# esp8266_shield.net
KiCad netlist of a schematic drawn in Altium Designer
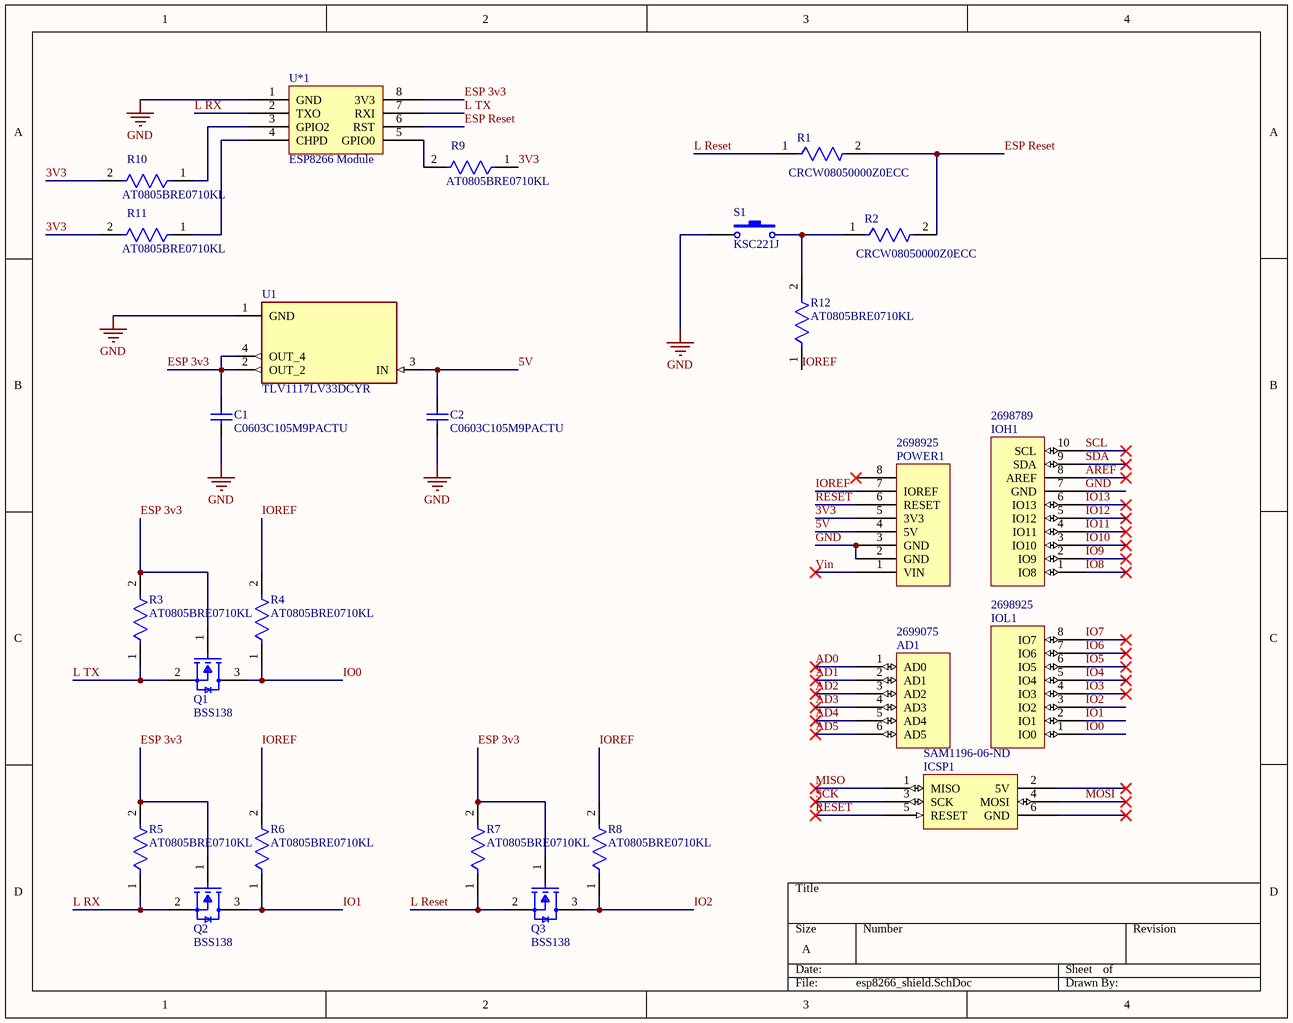
[diagram p0: esp8266_shield.SchDoc]

(export (version "E")
  (design (tool "Eeschema 10.0.6"))
  (components
    (comp (ref "AD1")
      (value "AD")
      (footprint "Header:Header 6x1 8.5mm")
      (fields (field (name "SUPPLIER PART NUMBER 4") "2699075"))
      (libsource (lib "Header") (part "AD"))
    )
    (comp (ref "C1")
      (value "C0603C105M9PACTU")
      (footprint "CAPC1608X90X35ML15T15")
      (fields (field (name "MANUFACTURER") "Kemet"))
      (libsource (lib "Altium Content Vault") (part "CAP"))
    )
    (comp (ref "C2")
      (value "C0603C105M9PACTU")
      (footprint "CAPC1608X90X35ML15T15")
      (fields (field (name "MANUFACTURER") "Kemet"))
      (libsource (lib "Altium Content Vault") (part "CAP"))
    )
    (comp (ref "ICSP1")
      (value "ICSP")
      (footprint "ICSP")
      (fields (field (name "SUPPLIER PART NUMBER 5") "SAM1196-06-ND"))
      (libsource (lib "Header") (part "ICSP"))
    )
    (comp (ref "IOH1")
      (value "IOH")
      (footprint "Header 10x1 8.5mm")
      (fields (field (name "SUPPLIER PART NUMBER 3") "2698789"))
      (libsource (lib "Header") (part "IOH"))
    )
    (comp (ref "IOL1")
      (value "IOL")
      (footprint "Header 8x1 8.5mm")
      (fields (field (name "SUPPLIER PART NUMBER 4") "2698925"))
      (libsource (lib "Header") (part "IOL"))
    )
    (comp (ref "POWER1")
      (value "POWER_UNO")
      (footprint "Header 8x1 8.5mm")
      (fields (field (name "SUPPLIER PART NUMBER 4") "2698925"))
      (libsource (lib "Header") (part "POWER_UNO"))
    )
    (comp (ref "Q1")
      (value "BSS138")
      (footprint "FP-318-08-IPC_B")
      (description "MOSFET N-CH 50V 220MA SOT-23")
      (libsource (lib "Altium Content Vault") (part "3b9c635fedb024a5347a57b145af9cc"))
    )
    (comp (ref "Q2")
      (value "BSS138")
      (footprint "FP-318-08-IPC_B")
      (description "MOSFET N-CH 50V 220MA SOT-23")
      (libsource (lib "Altium Content Vault") (part "3b9c635fedb024a5347a57b145af9cc"))
    )
    (comp (ref "Q3")
      (value "BSS138")
      (footprint "FP-318-08-IPC_B")
      (description "MOSFET N-CH 50V 220MA SOT-23")
      (libsource (lib "Altium Content Vault") (part "3b9c635fedb024a5347a57b145af9cc"))
    )
    (comp (ref "R1")
      (value "CRCW08050000Z0ECC")
      (footprint "FP-CRCW0805-Ce3-MFG")
      (libsource (lib "Altium Content Vault") (part "1029c3af85768c4190bb7ad29bc67b5"))
    )
    (comp (ref "R2")
      (value "CRCW08050000Z0ECC")
      (footprint "FP-CRCW0805-Ce3-MFG")
      (libsource (lib "Altium Content Vault") (part "1029c3af85768c4190bb7ad29bc67b5"))
    )
    (comp (ref "R3")
      (value "AT0805BRE0710KL")
      (footprint "FP-AT0805-IPC_C")
      (description "Thin Film Chip Resistors Automotive Grade 10kΩ 0.1% 50ppm/°C 0805")
      (libsource (lib "Altium Content Vault") (part "1029c3af85768c4190bb7ad29bc67b5"))
    )
    (comp (ref "R4")
      (value "AT0805BRE0710KL")
      (footprint "FP-AT0805-IPC_C")
      (description "Thin Film Chip Resistors Automotive Grade 10kΩ 0.1% 50ppm/°C 0805")
      (libsource (lib "Altium Content Vault") (part "1029c3af85768c4190bb7ad29bc67b5"))
    )
    (comp (ref "R5")
      (value "AT0805BRE0710KL")
      (footprint "FP-AT0805-IPC_C")
      (description "Thin Film Chip Resistors Automotive Grade 10kΩ 0.1% 50ppm/°C 0805")
      (libsource (lib "Altium Content Vault") (part "1029c3af85768c4190bb7ad29bc67b5"))
    )
    (comp (ref "R6")
      (value "AT0805BRE0710KL")
      (footprint "FP-AT0805-IPC_C")
      (description "Thin Film Chip Resistors Automotive Grade 10kΩ 0.1% 50ppm/°C 0805")
      (libsource (lib "Altium Content Vault") (part "1029c3af85768c4190bb7ad29bc67b5"))
    )
    (comp (ref "R7")
      (value "AT0805BRE0710KL")
      (footprint "FP-AT0805-IPC_C")
      (description "Thin Film Chip Resistors Automotive Grade 10kΩ 0.1% 50ppm/°C 0805")
      (libsource (lib "Altium Content Vault") (part "1029c3af85768c4190bb7ad29bc67b5"))
    )
    (comp (ref "R8")
      (value "AT0805BRE0710KL")
      (footprint "FP-AT0805-IPC_C")
      (description "Thin Film Chip Resistors Automotive Grade 10kΩ 0.1% 50ppm/°C 0805")
      (libsource (lib "Altium Content Vault") (part "1029c3af85768c4190bb7ad29bc67b5"))
    )
    (comp (ref "R9")
      (value "AT0805BRE0710KL")
      (footprint "FP-AT0805-IPC_C")
      (description "Thin Film Chip Resistors Automotive Grade 10kΩ 0.1% 50ppm/°C 0805")
      (libsource (lib "Altium Content Vault") (part "1029c3af85768c4190bb7ad29bc67b5"))
    )
    (comp (ref "R10")
      (value "AT0805BRE0710KL")
      (footprint "FP-AT0805-IPC_C")
      (description "Thin Film Chip Resistors Automotive Grade 10kΩ 0.1% 50ppm/°C 0805")
      (libsource (lib "Altium Content Vault") (part "1029c3af85768c4190bb7ad29bc67b5"))
    )
    (comp (ref "R11")
      (value "AT0805BRE0710KL")
      (footprint "FP-AT0805-IPC_C")
      (description "Thin Film Chip Resistors Automotive Grade 10kΩ 0.1% 50ppm/°C 0805")
      (libsource (lib "Altium Content Vault") (part "1029c3af85768c4190bb7ad29bc67b5"))
    )
    (comp (ref "R12")
      (value "AT0805BRE0710KL")
      (footprint "FP-AT0805-IPC_C")
      (description "Thin Film Chip Resistors Automotive Grade 10kΩ 0.1% 50ppm/°C 0805")
      (libsource (lib "Altium Content Vault") (part "1029c3af85768c4190bb7ad29bc67b5"))
    )
    (comp (ref "S1")
      (value "KSC221J")
      (footprint "ITT Cannon KSC2 Series")
      (description "SWITCH TACT SILVER J-LEAD")
      (libsource (lib "George Fox University") (part "SW-PB"))
    )
    (comp (ref "U*1")
      (value "ESP8266 Module")
      (footprint "Copy of ESP8266 2x4 Connector")
      (description "ESP8266 2x4 Module")
      (libsource (lib "George Fox University") (part "ESP8266 Module"))
    )
    (comp (ref "U1")
      (value "TLV1117LV33DCYR")
      (footprint "VREG_TLV1117LV33DCYR")
      (description "1-A, low-dropout voltage regulator")
      (fields (field (name "MF") "Texas Instruments") (field (name "DIGI-KEY_PART_NUMBER") "296-28778-2-ND"))
      (libsource (lib "George Fox University") (part "TLV1117LV33DCYR"))
    )
  )
  (nets
    (net (code "1") (name "/3V3") (class "Default")
      (node (ref "POWER1") (pin "5") (pinfunction "3V3_5") (pintype "power_in"))
      (node (ref "R10") (pin "2") (pinfunction "2_2") (pintype "passive"))
      (node (ref "R11") (pin "2") (pinfunction "2_2") (pintype "passive"))
      (node (ref "R9") (pin "1") (pinfunction "1_1") (pintype "passive"))
    )
    (net (code "2") (name "/5V") (class "Default")
      (node (ref "C2") (pin "2") (pinfunction "2_2") (pintype "passive"))
      (node (ref "POWER1") (pin "4") (pinfunction "5V_4") (pintype "power_in"))
      (node (ref "U1") (pin "3") (pinfunction "IN_3") (pintype "input"))
    )
    (net (code "4") (name "/AD0") (class "Default")
      (node (ref "AD1") (pin "1") (pinfunction "AD0_1") (pintype "bidirectional+no_connect"))
    )
    (net (code "5") (name "/AD1") (class "Default")
      (node (ref "AD1") (pin "2") (pinfunction "AD1_2") (pintype "bidirectional+no_connect"))
    )
    (net (code "6") (name "/AD2") (class "Default")
      (node (ref "AD1") (pin "3") (pinfunction "AD2_3") (pintype "bidirectional+no_connect"))
    )
    (net (code "7") (name "/AD3") (class "Default")
      (node (ref "AD1") (pin "4") (pinfunction "AD3_4") (pintype "bidirectional+no_connect"))
    )
    (net (code "8") (name "/AD4") (class "Default")
      (node (ref "AD1") (pin "5") (pinfunction "AD4_5") (pintype "bidirectional+no_connect"))
    )
    (net (code "9") (name "/AD5") (class "Default")
      (node (ref "AD1") (pin "6") (pinfunction "AD5_6") (pintype "bidirectional+no_connect"))
    )
    (net (code "10") (name "/AREF") (class "Default")
      (node (ref "IOH1") (pin "8") (pinfunction "AREF_8") (pintype "passive+no_connect"))
    )
    (net (code "11") (name "/ESP 3v3") (class "Default")
      (node (ref "C1") (pin "2") (pinfunction "2_2") (pintype "passive"))
      (node (ref "Q1") (pin "1") (pinfunction "G_1") (pintype "passive"))
      (node (ref "Q2") (pin "1") (pinfunction "G_1") (pintype "passive"))
      (node (ref "Q3") (pin "1") (pinfunction "G_1") (pintype "passive"))
      (node (ref "R3") (pin "2") (pinfunction "2_2") (pintype "passive"))
      (node (ref "R5") (pin "2") (pinfunction "2_2") (pintype "passive"))
      (node (ref "R7") (pin "2") (pinfunction "2_2") (pintype "passive"))
      (node (ref "U*1") (pin "8") (pinfunction "3V3_8") (pintype "passive"))
      (node (ref "U1") (pin "2") (pinfunction "OUT_2_2") (pintype "output"))
      (node (ref "U1") (pin "4") (pinfunction "OUT_4_4") (pintype "output"))
    )
    (net (code "12") (name "/ESP Reset") (class "Default")
      (node (ref "R1") (pin "2") (pinfunction "2_2") (pintype "passive"))
      (node (ref "R2") (pin "2") (pinfunction "2_2") (pintype "passive"))
      (node (ref "U*1") (pin "6") (pinfunction "RST_6") (pintype "passive"))
    )
    (net (code "13") (name "/IO0") (class "Default")
      (node (ref "IOL1") (pin "1") (pinfunction "IO0_1") (pintype "bidirectional"))
      (node (ref "Q1") (pin "3") (pinfunction "D_3") (pintype "passive"))
      (node (ref "R4") (pin "1") (pinfunction "1_1") (pintype "passive"))
    )
    (net (code "14") (name "/IO1") (class "Default")
      (node (ref "IOL1") (pin "2") (pinfunction "IO1_2") (pintype "bidirectional"))
      (node (ref "Q2") (pin "3") (pinfunction "D_3") (pintype "passive"))
      (node (ref "R6") (pin "1") (pinfunction "1_1") (pintype "passive"))
    )
    (net (code "15") (name "/IO2") (class "Default")
      (node (ref "IOL1") (pin "3") (pinfunction "IO2_3") (pintype "bidirectional"))
      (node (ref "Q3") (pin "3") (pinfunction "D_3") (pintype "passive"))
      (node (ref "R8") (pin "1") (pinfunction "1_1") (pintype "passive"))
    )
    (net (code "16") (name "/IO3") (class "Default")
      (node (ref "IOL1") (pin "4") (pinfunction "IO3_4") (pintype "bidirectional+no_connect"))
    )
    (net (code "17") (name "/IO4") (class "Default")
      (node (ref "IOL1") (pin "5") (pinfunction "IO4_5") (pintype "bidirectional+no_connect"))
    )
    (net (code "18") (name "/IO5") (class "Default")
      (node (ref "IOL1") (pin "6") (pinfunction "IO5_6") (pintype "bidirectional+no_connect"))
    )
    (net (code "19") (name "/IO6") (class "Default")
      (node (ref "IOL1") (pin "7") (pinfunction "IO6_7") (pintype "bidirectional+no_connect"))
    )
    (net (code "20") (name "/IO7") (class "Default")
      (node (ref "IOL1") (pin "8") (pinfunction "IO7_8") (pintype "bidirectional+no_connect"))
    )
    (net (code "21") (name "/IO8") (class "Default")
      (node (ref "IOH1") (pin "1") (pinfunction "IO8_1") (pintype "bidirectional+no_connect"))
    )
    (net (code "22") (name "/IO9") (class "Default")
      (node (ref "IOH1") (pin "2") (pinfunction "IO9_2") (pintype "bidirectional+no_connect"))
    )
    (net (code "23") (name "/IO10") (class "Default")
      (node (ref "IOH1") (pin "3") (pinfunction "IO10_3") (pintype "bidirectional+no_connect"))
    )
    (net (code "24") (name "/IO11") (class "Default")
      (node (ref "IOH1") (pin "4") (pinfunction "IO11_4") (pintype "bidirectional+no_connect"))
    )
    (net (code "25") (name "/IO12") (class "Default")
      (node (ref "IOH1") (pin "5") (pinfunction "IO12_5") (pintype "bidirectional+no_connect"))
    )
    (net (code "26") (name "/IO13") (class "Default")
      (node (ref "IOH1") (pin "6") (pinfunction "IO13_6") (pintype "bidirectional+no_connect"))
    )
    (net (code "27") (name "/IOREF") (class "Default")
      (node (ref "POWER1") (pin "7") (pinfunction "IOREF_7") (pintype "power_in"))
      (node (ref "R12") (pin "1") (pinfunction "1_1") (pintype "passive"))
      (node (ref "R4") (pin "2") (pinfunction "2_2") (pintype "passive"))
      (node (ref "R6") (pin "2") (pinfunction "2_2") (pintype "passive"))
      (node (ref "R8") (pin "2") (pinfunction "2_2") (pintype "passive"))
    )
    (net (code "28") (name "/L RX") (class "Default")
      (node (ref "Q2") (pin "2") (pinfunction "S_2") (pintype "passive"))
      (node (ref "R5") (pin "1") (pinfunction "1_1") (pintype "passive"))
      (node (ref "U*1") (pin "2") (pinfunction "TXO_2") (pintype "passive"))
    )
    (net (code "29") (name "/L Reset") (class "Default")
      (node (ref "Q3") (pin "2") (pinfunction "S_2") (pintype "passive"))
      (node (ref "R1") (pin "1") (pinfunction "1_1") (pintype "passive"))
      (node (ref "R7") (pin "1") (pinfunction "1_1") (pintype "passive"))
    )
    (net (code "30") (name "/L TX") (class "Default")
      (node (ref "Q1") (pin "2") (pinfunction "S_2") (pintype "passive"))
      (node (ref "R3") (pin "1") (pinfunction "1_1") (pintype "passive"))
      (node (ref "U*1") (pin "7") (pinfunction "RXI_7") (pintype "passive"))
    )
    (net (code "31") (name "/MISO") (class "Default")
      (node (ref "ICSP1") (pin "1") (pinfunction "MISO_1") (pintype "bidirectional+no_connect"))
    )
    (net (code "32") (name "/MOSI") (class "Default")
      (node (ref "ICSP1") (pin "4") (pinfunction "MOSI_4") (pintype "bidirectional+no_connect"))
    )
    (net (code "33") (name "/RESET") (class "Default")
      (node (ref "ICSP1") (pin "5") (pinfunction "RESET_5") (pintype "input"))
      (node (ref "POWER1") (pin "6") (pinfunction "RESET_6") (pintype "passive"))
    )
    (net (code "34") (name "/SCK") (class "Default")
      (node (ref "ICSP1") (pin "3") (pinfunction "SCK_3") (pintype "bidirectional+no_connect"))
    )
    (net (code "35") (name "/SCL") (class "Default")
      (node (ref "IOH1") (pin "10") (pinfunction "SCL_10") (pintype "bidirectional+no_connect"))
    )
    (net (code "36") (name "/SDA") (class "Default")
      (node (ref "IOH1") (pin "9") (pinfunction "SDA_9") (pintype "bidirectional+no_connect"))
    )
    (net (code "37") (name "/Vin") (class "Default")
      (node (ref "POWER1") (pin "1") (pinfunction "VIN_1") (pintype "power_in+no_connect"))
    )
    (net (code "38") (name "GND") (class "Default")
      (node (ref "C1") (pin "1") (pinfunction "1_1") (pintype "passive"))
      (node (ref "C2") (pin "1") (pinfunction "1_1") (pintype "passive"))
      (node (ref "IOH1") (pin "7") (pinfunction "GND_7") (pintype "power_in"))
      (node (ref "POWER1") (pin "2") (pinfunction "GND_2") (pintype "power_in"))
      (node (ref "POWER1") (pin "3") (pinfunction "GND_3") (pintype "power_in"))
      (node (ref "S1") (pin "1") (pinfunction "1_1") (pintype "passive"))
      (node (ref "U*1") (pin "1") (pinfunction "GND_1") (pintype "passive"))
      (node (ref "U1") (pin "1") (pinfunction "GND_1") (pintype "power_in"))
    )
    (net (code "39") (name "Net-(R12-Pad2)") (class "Default")
      (node (ref "R12") (pin "2") (pinfunction "2_2") (pintype "passive"))
      (node (ref "R2") (pin "1") (pinfunction "1_1") (pintype "passive"))
      (node (ref "S1") (pin "2") (pinfunction "2_2") (pintype "passive"))
    )
    (net (code "40") (name "Net-(U*1-CHPD)") (class "Default")
      (node (ref "R11") (pin "1") (pinfunction "1_1") (pintype "passive"))
      (node (ref "U*1") (pin "4") (pinfunction "CHPD_4") (pintype "passive"))
    )
    (net (code "41") (name "Net-(U*1-GPIO0)") (class "Default")
      (node (ref "R9") (pin "2") (pinfunction "2_2") (pintype "passive"))
      (node (ref "U*1") (pin "5") (pinfunction "GPIO0_5") (pintype "passive"))
    )
    (net (code "42") (name "Net-(U*1-GPIO2)") (class "Default")
      (node (ref "R10") (pin "1") (pinfunction "1_1") (pintype "passive"))
      (node (ref "U*1") (pin "3") (pinfunction "GPIO2_3") (pintype "passive"))
    )
    (net (code "43") (name "unconnected-(ICSP1-5V-Pad2)") (class "Default")
      (node (ref "ICSP1") (pin "2") (pinfunction "5V_2") (pintype "power_in+no_connect"))
    )
    (net (code "44") (name "unconnected-(ICSP1-GND-Pad6)") (class "Default")
      (node (ref "ICSP1") (pin "6") (pinfunction "GND_6") (pintype "power_in+no_connect"))
    )
    (net (code "45") (name "unconnected-(POWER1-Pad8)") (class "Default")
      (node (ref "POWER1") (pin "8") (pintype "passive+no_connect"))
    )
  )
)
